# IO_Shield.net
KiCad netlist of a schematic drawn in EAGLE
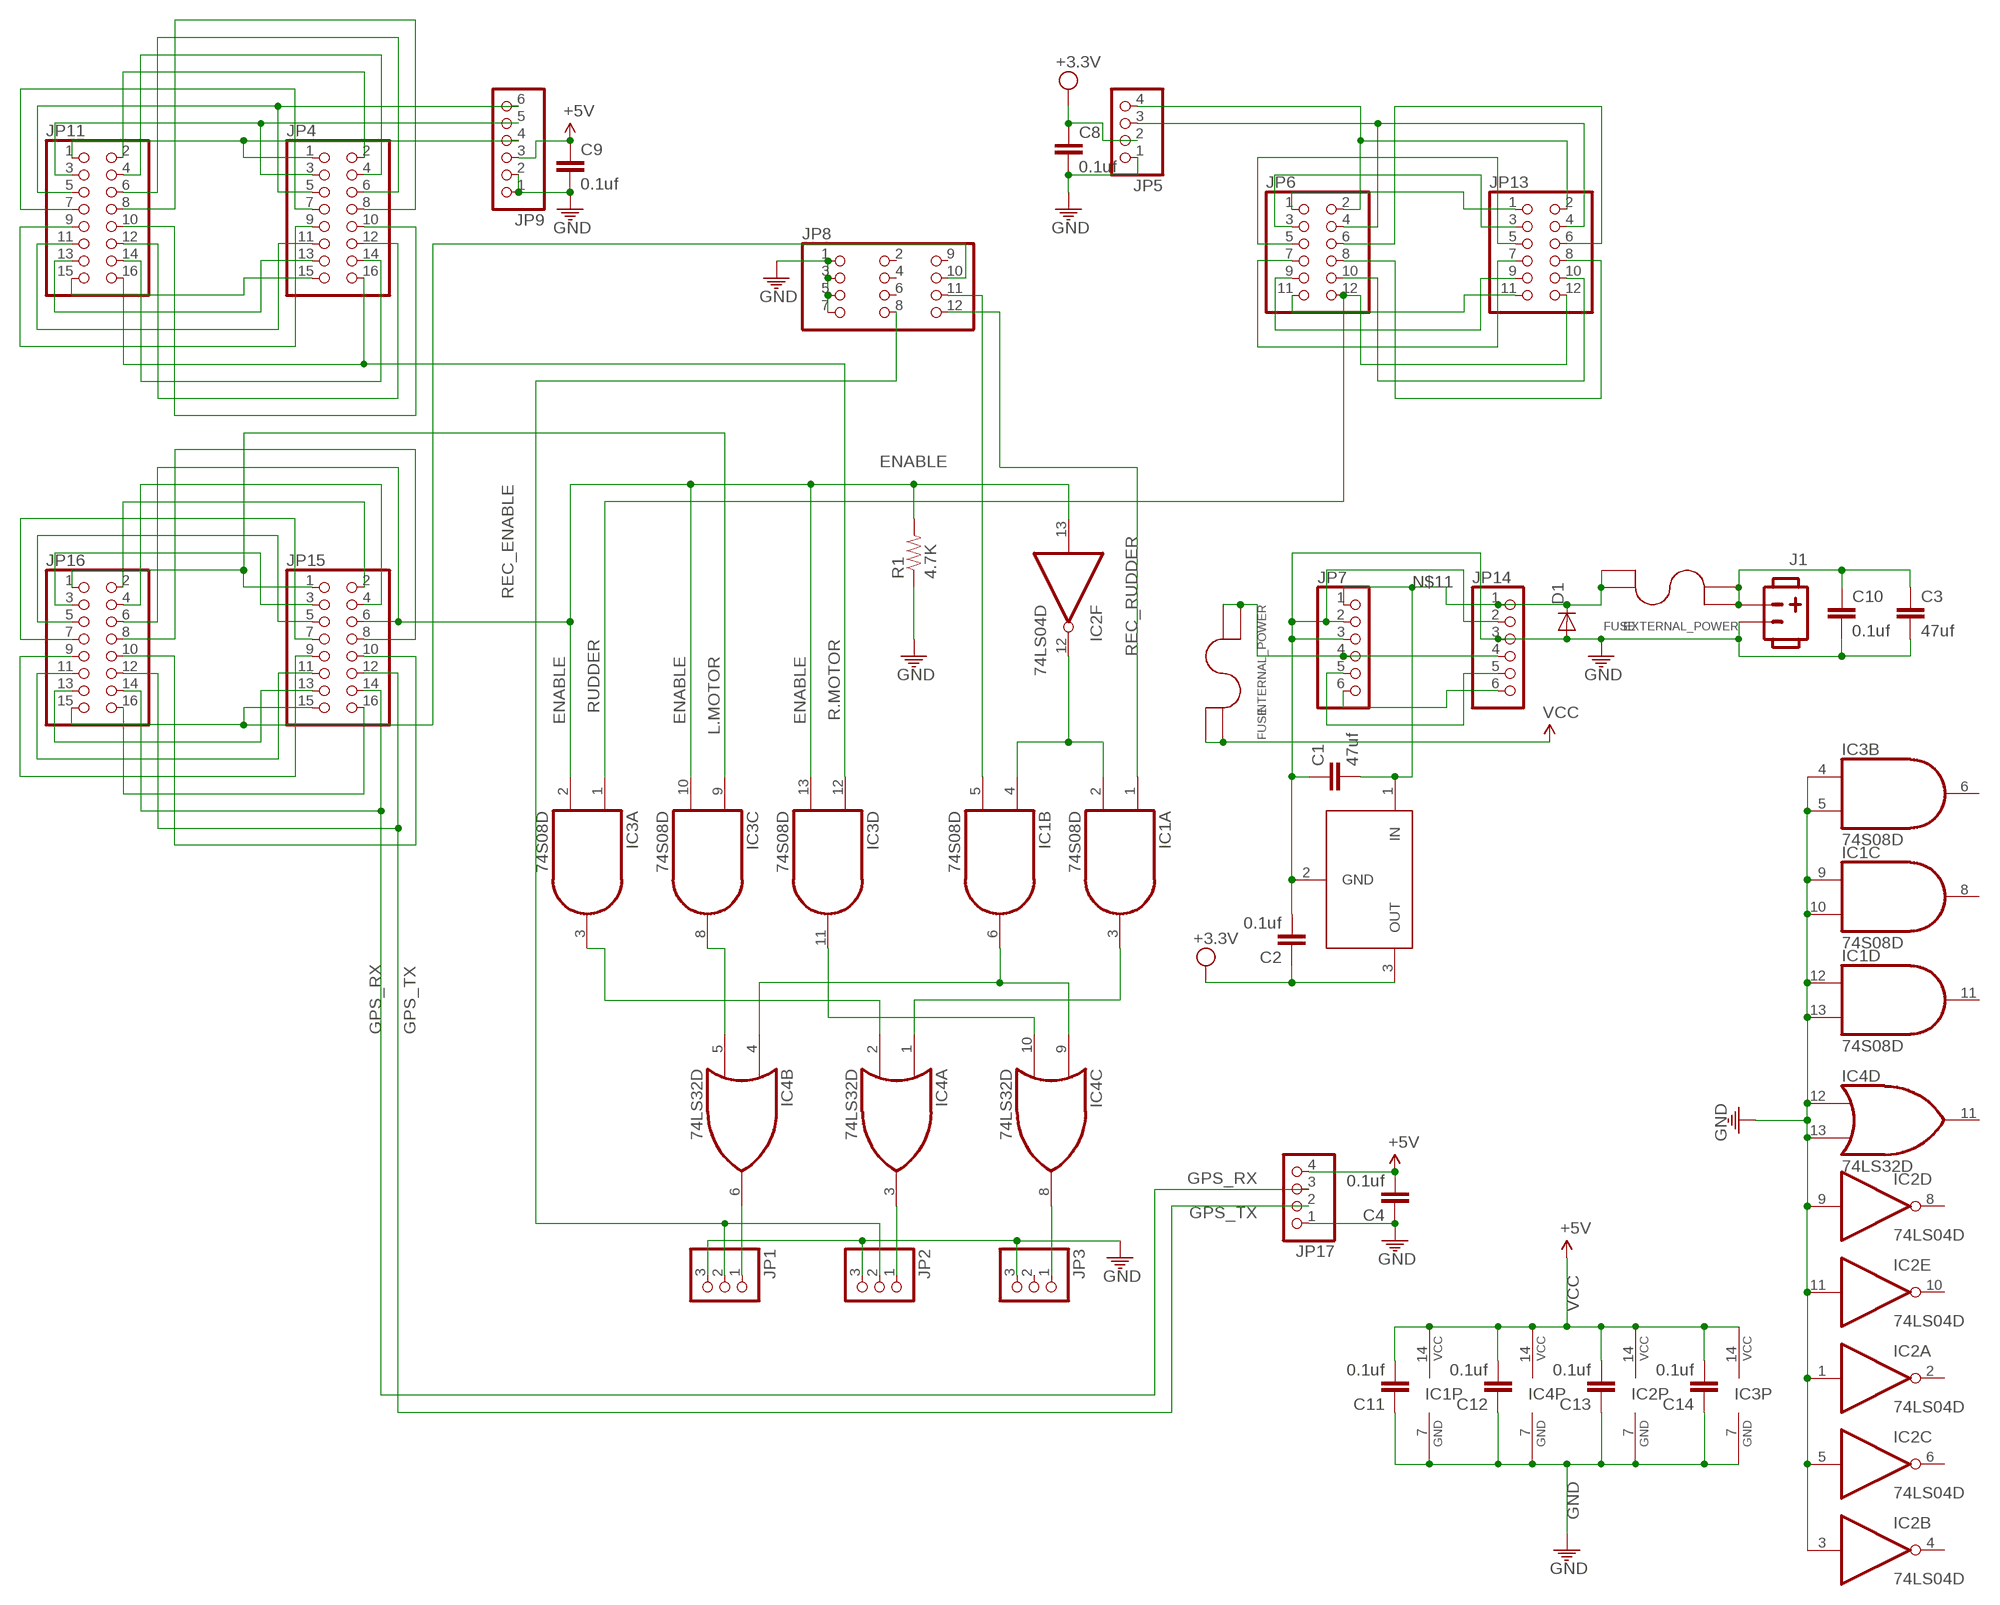
[diagram p0: schematic, sheet 1]

(export (version "E")
  (design (tool "Eeschema 10.0.6"))
  (components
    (comp (ref "C1")
      (value "47uf")
      (footprint "eagle-import:C0805")
      (libsource (lib "eagle-import") (part "C-EUC0805"))
    )
    (comp (ref "C2")
      (value "0.1uf")
      (footprint "eagle-import:C0805")
      (libsource (lib "eagle-import") (part "C-EUC0805"))
    )
    (comp (ref "C3")
      (value "47uf")
      (footprint "eagle-import:C0805")
      (libsource (lib "eagle-import") (part "C-EUC0805"))
    )
    (comp (ref "C4")
      (value "0.1uf")
      (footprint "eagle-import:C0805")
      (libsource (lib "eagle-import") (part "C-EUC0805"))
    )
    (comp (ref "C8")
      (value "0.1uf")
      (footprint "eagle-import:C0805")
      (libsource (lib "eagle-import") (part "C-EUC0805"))
    )
    (comp (ref "C9")
      (value "0.1uf")
      (footprint "eagle-import:C0805")
      (libsource (lib "eagle-import") (part "C-EUC0805"))
    )
    (comp (ref "C10")
      (value "0.1uf")
      (footprint "eagle-import:C0805")
      (libsource (lib "eagle-import") (part "C-EUC0805"))
    )
    (comp (ref "C11")
      (value "0.1uf")
      (footprint "eagle-import:C0805")
      (libsource (lib "eagle-import") (part "C-EUC0805"))
    )
    (comp (ref "C12")
      (value "0.1uf")
      (footprint "eagle-import:C0805")
      (libsource (lib "eagle-import") (part "C-EUC0805"))
    )
    (comp (ref "C13")
      (value "0.1uf")
      (footprint "eagle-import:C0805")
      (libsource (lib "eagle-import") (part "C-EUC0805"))
    )
    (comp (ref "C14")
      (value "0.1uf")
      (footprint "eagle-import:C0805")
      (libsource (lib "eagle-import") (part "C-EUC0805"))
    )
    (comp (ref "D1")
      (value "DIODEPTH")
      (footprint "eagle-import:DIODE-1N4001")
      (libsource (lib "eagle-import") (part "DIODEPTH"))
    )
    (comp (ref "EXTERNAL_POWER")
      (value "FUSE")
      (footprint "eagle-import:FUSE_2AG")
      (libsource (lib "eagle-import") (part "FUSE"))
    )
    (comp (ref "IC1")
      (value "74S08D")
      (footprint "eagle-import:SO14")
      (libsource (lib "eagle-import") (part "7408DS"))
    )
    (comp (ref "IC2")
      (value "74LS04D")
      (footprint "eagle-import:SO14")
      (libsource (lib "eagle-import") (part "7404DLS"))
    )
    (comp (ref "IC3")
      (value "74S08D")
      (footprint "eagle-import:SO14")
      (libsource (lib "eagle-import") (part "7408DS"))
    )
    (comp (ref "IC4")
      (value "74LS32D")
      (footprint "eagle-import:SO14")
      (libsource (lib "eagle-import") (part "7432DLS"))
    )
    (comp (ref "INTERNAL_POWER")
      (value "FUSE")
      (footprint "eagle-import:FUSE_2AG")
      (libsource (lib "eagle-import") (part "FUSE"))
    )
    (comp (ref "J1")
      (value "POW_CONNECTFEMALE-RA")
      (footprint "eagle-import:SOCKET-FEMALE_RA-3.96MM-2")
      (libsource (lib "eagle-import") (part "POW_CONNECTFEMALE-RA"))
    )
    (comp (ref "JP1")
      (value "PINHD-1X3/90")
      (footprint "eagle-import:1X03_90")
      (libsource (lib "eagle-import") (part "PINHD-1X3/90"))
    )
    (comp (ref "JP2")
      (value "PINHD-1X3/90")
      (footprint "eagle-import:1X03_90")
      (libsource (lib "eagle-import") (part "PINHD-1X3/90"))
    )
    (comp (ref "JP3")
      (value "PINHD-1X3/90")
      (footprint "eagle-import:1X03_90")
      (libsource (lib "eagle-import") (part "PINHD-1X3/90"))
    )
    (comp (ref "JP4")
      (value "PINHD-2X8")
      (footprint "eagle-import:2X08")
      (libsource (lib "eagle-import") (part "PINHD-2X8"))
    )
    (comp (ref "JP5")
      (value "PINHD-1X4")
      (footprint "eagle-import:1X04")
      (libsource (lib "eagle-import") (part "PINHD-1X4"))
    )
    (comp (ref "JP6")
      (value "PINHD-2X6")
      (footprint "eagle-import:2X06")
      (libsource (lib "eagle-import") (part "PINHD-2X6"))
    )
    (comp (ref "JP7")
      (value "PINHD-1X6")
      (footprint "eagle-import:1X06")
      (libsource (lib "eagle-import") (part "pinhead_PINHD-1X6"))
    )
    (comp (ref "JP8")
      (value "PINHD-2X4")
      (footprint "eagle-import:2X04")
      (libsource (lib "eagle-import") (part "PINHD-2X4"))
    )
    (comp (ref "JP9")
      (value "PINHD-1X6")
      (footprint "eagle-import:1X06")
      (libsource (lib "eagle-import") (part "PINHD-1X6"))
    )
    (comp (ref "JP11")
      (value "PINHD-2X8")
      (footprint "eagle-import:2X08")
      (libsource (lib "eagle-import") (part "PINHD-2X8"))
    )
    (comp (ref "JP13")
      (value "PINHD-2X6")
      (footprint "eagle-import:2X06")
      (libsource (lib "eagle-import") (part "PINHD-2X6"))
    )
    (comp (ref "JP14")
      (value "PINHD-1X6")
      (footprint "eagle-import:1X06")
      (libsource (lib "eagle-import") (part "pinhead_PINHD-1X6"))
    )
    (comp (ref "JP15")
      (value "PINHD-2X8")
      (footprint "eagle-import:2X08")
      (libsource (lib "eagle-import") (part "PINHD-2X8"))
    )
    (comp (ref "JP16")
      (value "PINHD-2X8")
      (footprint "eagle-import:2X08")
      (libsource (lib "eagle-import") (part "PINHD-2X8"))
    )
    (comp (ref "JP17")
      (value "PINHD-1X4")
      (footprint "eagle-import:1X04")
      (libsource (lib "eagle-import") (part "pinhead_PINHD-1X4"))
    )
    (comp (ref "R1")
      (value "4.7K")
      (footprint "eagle-import:0805")
      (libsource (lib "eagle-import") (part "RESISTOR0805-RES"))
    )
    (comp (ref "U$1")
      (value "LM3940IMP-3.3")
      (footprint "eagle-import:SOT223")
      (libsource (lib "eagle-import") (part "LM3940IMP-3.3"))
    )
  )
  (nets
    (net (code "1") (name "+3.3V") (class "Default")
      (node (ref "C2") (pin "1") (pinfunction "1_1") (pintype "passive"))
      (node (ref "C8") (pin "1") (pinfunction "1_1") (pintype "passive"))
      (node (ref "JP5") (pin "2") (pinfunction "2_2") (pintype "passive"))
      (node (ref "U$1") (pin "3") (pinfunction "OUT_3") (pintype "power_in"))
    )
    (net (code "2") (name "+5V") (class "Default")
      (node (ref "C11") (pin "2") (pinfunction "2_2") (pintype "passive"))
      (node (ref "C12") (pin "2") (pinfunction "2_2") (pintype "passive"))
      (node (ref "C13") (pin "2") (pinfunction "2_2") (pintype "passive"))
      (node (ref "C14") (pin "2") (pinfunction "2_2") (pintype "passive"))
      (node (ref "C4") (pin "2") (pinfunction "2_2") (pintype "passive"))
      (node (ref "C9") (pin "1") (pinfunction "1_1") (pintype "passive"))
      (node (ref "IC1") (pin "14") (pinfunction "VCC_14") (pintype "power_in"))
      (node (ref "IC2") (pin "14") (pinfunction "VCC_14") (pintype "power_in"))
      (node (ref "IC3") (pin "14") (pinfunction "VCC_14") (pintype "power_in"))
      (node (ref "IC4") (pin "14") (pinfunction "VCC_14") (pintype "power_in"))
      (node (ref "INTERNAL_POWER") (pin "P$3") (pinfunction "3_P$3") (pintype "bidirectional"))
      (node (ref "INTERNAL_POWER") (pin "P$4") (pinfunction "4_P$4") (pintype "bidirectional"))
      (node (ref "JP17") (pin "4") (pinfunction "4_4") (pintype "passive"))
      (node (ref "JP9") (pin "3") (pinfunction "3_3") (pintype "passive"))
    )
    (net (code "3") (name "/ENABLE") (class "Default")
      (node (ref "IC2") (pin "13") (pinfunction "I_13") (pintype "input"))
      (node (ref "IC3") (pin "10") (pinfunction "I1_10") (pintype "input"))
      (node (ref "IC3") (pin "13") (pinfunction "I1_13") (pintype "input"))
      (node (ref "IC3") (pin "2") (pinfunction "I1_2") (pintype "input"))
      (node (ref "JP15") (pin "6") (pinfunction "6_6") (pintype "passive"))
      (node (ref "JP16") (pin "6") (pinfunction "6_6") (pintype "passive"))
      (node (ref "R1") (pin "2") (pinfunction "2_2") (pintype "passive"))
    )
    (net (code "4") (name "/GPS_RX") (class "Default")
      (node (ref "JP15") (pin "14") (pinfunction "14_14") (pintype "passive"))
      (node (ref "JP16") (pin "14") (pinfunction "14_14") (pintype "passive"))
      (node (ref "JP17") (pin "3") (pinfunction "3_3") (pintype "passive"))
    )
    (net (code "5") (name "/GPS_TX") (class "Default")
      (node (ref "JP15") (pin "12") (pinfunction "12_12") (pintype "passive"))
      (node (ref "JP16") (pin "12") (pinfunction "12_12") (pintype "passive"))
      (node (ref "JP17") (pin "2") (pinfunction "2_2") (pintype "passive"))
    )
    (net (code "6") (name "/L.MOTOR") (class "Default")
      (node (ref "IC3") (pin "9") (pinfunction "I0_9") (pintype "input"))
      (node (ref "JP15") (pin "1") (pinfunction "1_1") (pintype "passive"))
      (node (ref "JP16") (pin "1") (pinfunction "1_1") (pintype "passive"))
    )
    (net (code "7") (name "/N$11") (class "Default")
      (node (ref "C1") (pin "2") (pinfunction "2_2") (pintype "passive"))
      (node (ref "D1") (pin "C") (pinfunction "C_C") (pintype "passive"))
      (node (ref "EXTERNAL_POWER") (pin "P$3") (pinfunction "3_P$3") (pintype "bidirectional"))
      (node (ref "EXTERNAL_POWER") (pin "P$4") (pinfunction "4_P$4") (pintype "bidirectional"))
      (node (ref "JP14") (pin "1") (pinfunction "1_1") (pintype "passive"))
      (node (ref "JP7") (pin "1") (pinfunction "1_1") (pintype "passive"))
      (node (ref "U$1") (pin "1") (pinfunction "IN_1") (pintype "power_in"))
    )
    (net (code "8") (name "/R.MOTOR") (class "Default")
      (node (ref "IC3") (pin "12") (pinfunction "I0_12") (pintype "input"))
      (node (ref "JP11") (pin "16") (pinfunction "16_16") (pintype "passive"))
      (node (ref "JP4") (pin "16") (pinfunction "16_16") (pintype "passive"))
    )
    (net (code "9") (name "/REC_ENABLE") (class "Default")
      (node (ref "JP15") (pin "16") (pinfunction "16_16") (pintype "passive"))
      (node (ref "JP16") (pin "16") (pinfunction "16_16") (pintype "passive"))
    )
    (net (code "10") (name "/REC_RUDDER") (class "Default")
      (node (ref "IC1") (pin "1") (pinfunction "I0_1") (pintype "input"))
      (node (ref "JP8") (pin "12") (pinfunction "12_12") (pintype "passive"))
    )
    (net (code "11") (name "/RUDDER") (class "Default")
      (node (ref "IC3") (pin "1") (pinfunction "I0_1") (pintype "input"))
      (node (ref "JP13") (pin "12") (pinfunction "12_12") (pintype "passive"))
      (node (ref "JP6") (pin "12") (pinfunction "12_12") (pintype "passive"))
    )
    (net (code "12") (name "GND") (class "Default")
      (node (ref "C1") (pin "1") (pinfunction "1_1") (pintype "passive"))
      (node (ref "C10") (pin "2") (pinfunction "2_2") (pintype "passive"))
      (node (ref "C11") (pin "1") (pinfunction "1_1") (pintype "passive"))
      (node (ref "C12") (pin "1") (pinfunction "1_1") (pintype "passive"))
      (node (ref "C13") (pin "1") (pinfunction "1_1") (pintype "passive"))
      (node (ref "C14") (pin "1") (pinfunction "1_1") (pintype "passive"))
      (node (ref "C2") (pin "2") (pinfunction "2_2") (pintype "passive"))
      (node (ref "C3") (pin "2") (pinfunction "2_2") (pintype "passive"))
      (node (ref "C4") (pin "1") (pinfunction "1_1") (pintype "passive"))
      (node (ref "C8") (pin "2") (pinfunction "2_2") (pintype "passive"))
      (node (ref "C9") (pin "2") (pinfunction "2_2") (pintype "passive"))
      (node (ref "D1") (pin "A") (pinfunction "A_A") (pintype "passive"))
      (node (ref "IC1") (pin "10") (pinfunction "I1_10") (pintype "input"))
      (node (ref "IC1") (pin "12") (pinfunction "I0_12") (pintype "input"))
      (node (ref "IC1") (pin "13") (pinfunction "I1_13") (pintype "input"))
      (node (ref "IC1") (pin "7") (pinfunction "GND_7") (pintype "power_in"))
      (node (ref "IC1") (pin "9") (pinfunction "I0_9") (pintype "input"))
      (node (ref "IC2") (pin "1") (pinfunction "I_1") (pintype "input"))
      (node (ref "IC2") (pin "11") (pinfunction "I_11") (pintype "input"))
      (node (ref "IC2") (pin "3") (pinfunction "I_3") (pintype "input"))
      (node (ref "IC2") (pin "5") (pinfunction "I_5") (pintype "input"))
      (node (ref "IC2") (pin "7") (pinfunction "GND_7") (pintype "power_in"))
      (node (ref "IC2") (pin "9") (pinfunction "I_9") (pintype "input"))
      (node (ref "IC3") (pin "4") (pinfunction "I0_4") (pintype "input"))
      (node (ref "IC3") (pin "5") (pinfunction "I1_5") (pintype "input"))
      (node (ref "IC3") (pin "7") (pinfunction "GND_7") (pintype "power_in"))
      (node (ref "IC4") (pin "12") (pinfunction "I0_12") (pintype "input"))
      (node (ref "IC4") (pin "13") (pinfunction "I1_13") (pintype "input"))
      (node (ref "IC4") (pin "7") (pinfunction "GND_7") (pintype "power_in"))
      (node (ref "J1") (pin "2") (pinfunction "2_2") (pintype "passive"))
      (node (ref "JP1") (pin "3") (pinfunction "3_3") (pintype "passive"))
      (node (ref "JP14") (pin "2") (pinfunction "2_2") (pintype "passive"))
      (node (ref "JP14") (pin "3") (pinfunction "3_3") (pintype "passive"))
      (node (ref "JP17") (pin "1") (pinfunction "1_1") (pintype "passive"))
      (node (ref "JP2") (pin "3") (pinfunction "3_3") (pintype "passive"))
      (node (ref "JP3") (pin "3") (pinfunction "3_3") (pintype "passive"))
      (node (ref "JP5") (pin "1") (pinfunction "1_1") (pintype "passive"))
      (node (ref "JP7") (pin "2") (pinfunction "2_2") (pintype "passive"))
      (node (ref "JP7") (pin "3") (pinfunction "3_3") (pintype "passive"))
      (node (ref "JP8") (pin "1") (pinfunction "1_1") (pintype "passive"))
      (node (ref "JP8") (pin "3") (pinfunction "3_3") (pintype "passive"))
      (node (ref "JP8") (pin "5") (pinfunction "5_5") (pintype "passive"))
      (node (ref "JP8") (pin "7") (pinfunction "7_7") (pintype "passive"))
      (node (ref "JP9") (pin "1") (pinfunction "1_1") (pintype "passive"))
      (node (ref "JP9") (pin "2") (pinfunction "2_2") (pintype "passive"))
      (node (ref "R1") (pin "1") (pinfunction "1_1") (pintype "passive"))
      (node (ref "U$1") (pin "2") (pinfunction "GND_2") (pintype "power_in"))
    )
    (net (code "13") (name "Net-(EXTERNAL_POWER-1)") (class "Default")
      (node (ref "C10") (pin "1") (pinfunction "1_1") (pintype "passive"))
      (node (ref "C3") (pin "1") (pinfunction "1_1") (pintype "passive"))
      (node (ref "EXTERNAL_POWER") (pin "P$1") (pinfunction "1_P$1") (pintype "bidirectional"))
      (node (ref "EXTERNAL_POWER") (pin "P$2") (pinfunction "2_P$2") (pintype "bidirectional"))
      (node (ref "J1") (pin "1") (pinfunction "1_1") (pintype "passive"))
    )
    (net (code "14") (name "Net-(IC1A-I1)") (class "Default")
      (node (ref "IC1") (pin "2") (pinfunction "I1_2") (pintype "input"))
      (node (ref "IC1") (pin "4") (pinfunction "I0_4") (pintype "input"))
      (node (ref "IC2") (pin "12") (pinfunction "O_12") (pintype "output"))
    )
    (net (code "15") (name "Net-(IC1A-O)") (class "Default")
      (node (ref "IC1") (pin "3") (pinfunction "O_3") (pintype "output"))
      (node (ref "IC4") (pin "1") (pinfunction "I0_1") (pintype "input"))
    )
    (net (code "16") (name "Net-(IC1B-I1)") (class "Default")
      (node (ref "IC1") (pin "5") (pinfunction "I1_5") (pintype "input"))
      (node (ref "JP8") (pin "11") (pinfunction "11_11") (pintype "passive"))
    )
    (net (code "17") (name "Net-(IC1B-O)") (class "Default")
      (node (ref "IC1") (pin "6") (pinfunction "O_6") (pintype "output"))
      (node (ref "IC4") (pin "4") (pinfunction "I0_4") (pintype "input"))
      (node (ref "IC4") (pin "9") (pinfunction "I0_9") (pintype "input"))
    )
    (net (code "18") (name "Net-(IC3A-O)") (class "Default")
      (node (ref "IC3") (pin "3") (pinfunction "O_3") (pintype "output"))
      (node (ref "IC4") (pin "2") (pinfunction "I1_2") (pintype "input"))
    )
    (net (code "19") (name "Net-(IC3C-O)") (class "Default")
      (node (ref "IC3") (pin "8") (pinfunction "O_8") (pintype "output"))
      (node (ref "IC4") (pin "5") (pinfunction "I1_5") (pintype "input"))
    )
    (net (code "20") (name "Net-(IC3D-O)") (class "Default")
      (node (ref "IC3") (pin "11") (pinfunction "O_11") (pintype "output"))
      (node (ref "IC4") (pin "10") (pinfunction "I1_10") (pintype "input"))
    )
    (net (code "21") (name "Net-(IC4A-O)") (class "Default")
      (node (ref "IC4") (pin "3") (pinfunction "O_3") (pintype "output"))
      (node (ref "JP2") (pin "1") (pinfunction "1_1") (pintype "passive"))
    )
    (net (code "22") (name "Net-(IC4B-O)") (class "Default")
      (node (ref "IC4") (pin "6") (pinfunction "O_6") (pintype "output"))
      (node (ref "JP1") (pin "1") (pinfunction "1_1") (pintype "passive"))
    )
    (net (code "23") (name "Net-(IC4C-O)") (class "Default")
      (node (ref "IC4") (pin "8") (pinfunction "O_8") (pintype "output"))
      (node (ref "JP3") (pin "1") (pinfunction "1_1") (pintype "passive"))
    )
    (net (code "24") (name "Net-(INTERNAL_POWER-1)") (class "Default")
      (node (ref "INTERNAL_POWER") (pin "P$1") (pinfunction "1_P$1") (pintype "bidirectional"))
      (node (ref "INTERNAL_POWER") (pin "P$2") (pinfunction "2_P$2") (pintype "bidirectional"))
      (node (ref "JP14") (pin "4") (pinfunction "4_4") (pintype "passive"))
      (node (ref "JP7") (pin "4") (pinfunction "4_4") (pintype "passive"))
    )
    (net (code "25") (name "Net-(JP1-Pad2)") (class "Default")
      (node (ref "JP1") (pin "2") (pinfunction "2_2") (pintype "passive"))
      (node (ref "JP2") (pin "2") (pinfunction "2_2") (pintype "passive"))
      (node (ref "JP8") (pin "8") (pinfunction "8_8") (pintype "passive"))
    )
    (net (code "26") (name "Net-(JP8-9)") (class "Default")
      (node (ref "JP15") (pin "15") (pinfunction "15_15") (pintype "passive"))
      (node (ref "JP16") (pin "15") (pinfunction "15_15") (pintype "passive"))
      (node (ref "JP8") (pin "10") (pinfunction "9_10") (pintype "passive"))
    )
    (net (code "27") (name "Net-(JP11-Pad1)") (class "Default")
      (node (ref "JP11") (pin "1") (pinfunction "1_1") (pintype "passive"))
      (node (ref "JP4") (pin "1") (pinfunction "1_1") (pintype "passive"))
      (node (ref "JP9") (pin "4") (pinfunction "4_4") (pintype "passive"))
    )
    (net (code "28") (name "Net-(JP11-Pad2)") (class "Default")
      (node (ref "JP11") (pin "2") (pinfunction "2_2") (pintype "passive"))
      (node (ref "JP4") (pin "2") (pinfunction "2_2") (pintype "passive"))
    )
    (net (code "29") (name "Net-(JP11-Pad3)") (class "Default")
      (node (ref "JP11") (pin "3") (pinfunction "3_3") (pintype "passive"))
      (node (ref "JP4") (pin "3") (pinfunction "3_3") (pintype "passive"))
      (node (ref "JP9") (pin "5") (pinfunction "5_5") (pintype "passive"))
    )
    (net (code "30") (name "Net-(JP11-Pad4)") (class "Default")
      (node (ref "JP11") (pin "4") (pinfunction "4_4") (pintype "passive"))
      (node (ref "JP4") (pin "4") (pinfunction "4_4") (pintype "passive"))
    )
    (net (code "31") (name "Net-(JP11-Pad5)") (class "Default")
      (node (ref "JP11") (pin "5") (pinfunction "5_5") (pintype "passive"))
      (node (ref "JP4") (pin "5") (pinfunction "5_5") (pintype "passive"))
      (node (ref "JP9") (pin "6") (pinfunction "6_6") (pintype "passive"))
    )
    (net (code "32") (name "Net-(JP11-Pad6)") (class "Default")
      (node (ref "JP11") (pin "6") (pinfunction "6_6") (pintype "passive"))
      (node (ref "JP4") (pin "6") (pinfunction "6_6") (pintype "passive"))
    )
    (net (code "33") (name "Net-(JP11-Pad7)") (class "Default")
      (node (ref "JP11") (pin "7") (pinfunction "7_7") (pintype "passive"))
      (node (ref "JP4") (pin "7") (pinfunction "7_7") (pintype "passive"))
    )
    (net (code "34") (name "Net-(JP11-Pad8)") (class "Default")
      (node (ref "JP11") (pin "8") (pinfunction "8_8") (pintype "passive"))
      (node (ref "JP4") (pin "8") (pinfunction "8_8") (pintype "passive"))
    )
    (net (code "35") (name "Net-(JP11-Pad9)") (class "Default")
      (node (ref "JP11") (pin "9") (pinfunction "9_9") (pintype "passive"))
      (node (ref "JP4") (pin "9") (pinfunction "9_9") (pintype "passive"))
    )
    (net (code "36") (name "Net-(JP11-Pad10)") (class "Default")
      (node (ref "JP11") (pin "10") (pinfunction "10_10") (pintype "passive"))
      (node (ref "JP4") (pin "10") (pinfunction "10_10") (pintype "passive"))
    )
    (net (code "37") (name "Net-(JP11-Pad11)") (class "Default")
      (node (ref "JP11") (pin "11") (pinfunction "11_11") (pintype "passive"))
      (node (ref "JP4") (pin "11") (pinfunction "11_11") (pintype "passive"))
    )
    (net (code "38") (name "Net-(JP11-Pad12)") (class "Default")
      (node (ref "JP11") (pin "12") (pinfunction "12_12") (pintype "passive"))
      (node (ref "JP4") (pin "12") (pinfunction "12_12") (pintype "passive"))
    )
    (net (code "39") (name "Net-(JP11-Pad13)") (class "Default")
      (node (ref "JP11") (pin "13") (pinfunction "13_13") (pintype "passive"))
      (node (ref "JP4") (pin "13") (pinfunction "13_13") (pintype "passive"))
    )
    (net (code "40") (name "Net-(JP11-Pad14)") (class "Default")
      (node (ref "JP11") (pin "14") (pinfunction "14_14") (pintype "passive"))
      (node (ref "JP4") (pin "14") (pinfunction "14_14") (pintype "passive"))
    )
    (net (code "41") (name "Net-(JP11-Pad15)") (class "Default")
      (node (ref "JP11") (pin "15") (pinfunction "15_15") (pintype "passive"))
      (node (ref "JP4") (pin "15") (pinfunction "15_15") (pintype "passive"))
    )
    (net (code "42") (name "Net-(JP13-Pad1)") (class "Default")
      (node (ref "JP13") (pin "1") (pinfunction "1_1") (pintype "passive"))
      (node (ref "JP6") (pin "1") (pinfunction "1_1") (pintype "passive"))
    )
    (net (code "43") (name "Net-(JP13-Pad2)") (class "Default")
      (node (ref "JP13") (pin "2") (pinfunction "2_2") (pintype "passive"))
      (node (ref "JP5") (pin "4") (pinfunction "4_4") (pintype "passive"))
      (node (ref "JP6") (pin "2") (pinfunction "2_2") (pintype "passive"))
    )
    (net (code "44") (name "Net-(JP13-Pad3)") (class "Default")
      (node (ref "JP13") (pin "3") (pinfunction "3_3") (pintype "passive"))
      (node (ref "JP6") (pin "3") (pinfunction "3_3") (pintype "passive"))
    )
    (net (code "45") (name "Net-(JP13-Pad4)") (class "Default")
      (node (ref "JP13") (pin "4") (pinfunction "4_4") (pintype "passive"))
      (node (ref "JP5") (pin "3") (pinfunction "3_3") (pintype "passive"))
      (node (ref "JP6") (pin "4") (pinfunction "4_4") (pintype "passive"))
    )
    (net (code "46") (name "Net-(JP13-Pad5)") (class "Default")
      (node (ref "JP13") (pin "5") (pinfunction "5_5") (pintype "passive"))
      (node (ref "JP6") (pin "5") (pinfunction "5_5") (pintype "passive"))
    )
    (net (code "47") (name "Net-(JP13-Pad6)") (class "Default")
      (node (ref "JP13") (pin "6") (pinfunction "6_6") (pintype "passive"))
      (node (ref "JP6") (pin "6") (pinfunction "6_6") (pintype "passive"))
    )
    (net (code "48") (name "Net-(JP13-Pad7)") (class "Default")
      (node (ref "JP13") (pin "7") (pinfunction "7_7") (pintype "passive"))
      (node (ref "JP6") (pin "7") (pinfunction "7_7") (pintype "passive"))
    )
    (net (code "49") (name "Net-(JP13-Pad8)") (class "Default")
      (node (ref "JP13") (pin "8") (pinfunction "8_8") (pintype "passive"))
      (node (ref "JP6") (pin "8") (pinfunction "8_8") (pintype "passive"))
    )
    (net (code "50") (name "Net-(JP13-Pad9)") (class "Default")
      (node (ref "JP13") (pin "9") (pinfunction "9_9") (pintype "passive"))
      (node (ref "JP6") (pin "9") (pinfunction "9_9") (pintype "passive"))
    )
    (net (code "51") (name "Net-(JP13-Pad10)") (class "Default")
      (node (ref "JP13") (pin "10") (pinfunction "10_10") (pintype "passive"))
      (node (ref "JP6") (pin "10") (pinfunction "10_10") (pintype "passive"))
    )
    (net (code "52") (name "Net-(JP13-Pad11)") (class "Default")
      (node (ref "JP13") (pin "11") (pinfunction "11_11") (pintype "passive"))
      (node (ref "JP6") (pin "11") (pinfunction "11_11") (pintype "passive"))
    )
    (net (code "53") (name "Net-(JP14-Pad5)") (class "Default")
      (node (ref "JP14") (pin "5") (pinfunction "5_5") (pintype "passive"))
      (node (ref "JP7") (pin "5") (pinfunction "5_5") (pintype "passive"))
    )
    (net (code "54") (name "Net-(JP14-Pad6)") (class "Default")
      (node (ref "JP14") (pin "6") (pinfunction "6_6") (pintype "passive"))
      (node (ref "JP7") (pin "6") (pinfunction "6_6") (pintype "passive"))
    )
    (net (code "55") (name "Net-(JP15-Pad2)") (class "Default")
      (node (ref "JP15") (pin "2") (pinfunction "2_2") (pintype "passive"))
      (node (ref "JP16") (pin "2") (pinfunction "2_2") (pintype "passive"))
    )
    (net (code "56") (name "Net-(JP15-Pad3)") (class "Default")
      (node (ref "JP15") (pin "3") (pinfunction "3_3") (pintype "passive"))
      (node (ref "JP16") (pin "3") (pinfunction "3_3") (pintype "passive"))
    )
    (net (code "57") (name "Net-(JP15-Pad4)") (class "Default")
      (node (ref "JP15") (pin "4") (pinfunction "4_4") (pintype "passive"))
      (node (ref "JP16") (pin "4") (pinfunction "4_4") (pintype "passive"))
    )
    (net (code "58") (name "Net-(JP15-Pad5)") (class "Default")
      (node (ref "JP15") (pin "5") (pinfunction "5_5") (pintype "passive"))
      (node (ref "JP16") (pin "5") (pinfunction "5_5") (pintype "passive"))
    )
    (net (code "59") (name "Net-(JP15-Pad7)") (class "Default")
      (node (ref "JP15") (pin "7") (pinfunction "7_7") (pintype "passive"))
      (node (ref "JP16") (pin "7") (pinfunction "7_7") (pintype "passive"))
    )
    (net (code "60") (name "Net-(JP15-Pad8)") (class "Default")
      (node (ref "JP15") (pin "8") (pinfunction "8_8") (pintype "passive"))
      (node (ref "JP16") (pin "8") (pinfunction "8_8") (pintype "passive"))
    )
    (net (code "61") (name "Net-(JP15-Pad9)") (class "Default")
      (node (ref "JP15") (pin "9") (pinfunction "9_9") (pintype "passive"))
      (node (ref "JP16") (pin "9") (pinfunction "9_9") (pintype "passive"))
    )
    (net (code "62") (name "Net-(JP15-Pad10)") (class "Default")
      (node (ref "JP15") (pin "10") (pinfunction "10_10") (pintype "passive"))
      (node (ref "JP16") (pin "10") (pinfunction "10_10") (pintype "passive"))
    )
    (net (code "63") (name "Net-(JP15-Pad11)") (class "Default")
      (node (ref "JP15") (pin "11") (pinfunction "11_11") (pintype "passive"))
      (node (ref "JP16") (pin "11") (pinfunction "11_11") (pintype "passive"))
    )
    (net (code "64") (name "Net-(JP15-Pad13)") (class "Default")
      (node (ref "JP15") (pin "13") (pinfunction "13_13") (pintype "passive"))
      (node (ref "JP16") (pin "13") (pinfunction "13_13") (pintype "passive"))
    )
    (net (code "65") (name "unconnected-(IC1C-O-Pad8)") (class "Default")
      (node (ref "IC1") (pin "8") (pinfunction "O_8") (pintype "output"))
    )
    (net (code "66") (name "unconnected-(IC1D-O-Pad11)") (class "Default")
      (node (ref "IC1") (pin "11") (pinfunction "O_11") (pintype "output"))
    )
    (net (code "67") (name "unconnected-(IC2A-O-Pad2)") (class "Default")
      (node (ref "IC2") (pin "2") (pinfunction "O_2") (pintype "output"))
    )
    (net (code "68") (name "unconnected-(IC2B-O-Pad4)") (class "Default")
      (node (ref "IC2") (pin "4") (pinfunction "O_4") (pintype "output"))
    )
    (net (code "69") (name "unconnected-(IC2C-O-Pad6)") (class "Default")
      (node (ref "IC2") (pin "6") (pinfunction "O_6") (pintype "output"))
    )
    (net (code "70") (name "unconnected-(IC2D-O-Pad8)") (class "Default")
      (node (ref "IC2") (pin "8") (pinfunction "O_8") (pintype "output"))
    )
    (net (code "71") (name "unconnected-(IC2E-O-Pad10)") (class "Default")
      (node (ref "IC2") (pin "10") (pinfunction "O_10") (pintype "output"))
    )
    (net (code "72") (name "unconnected-(IC3B-O-Pad6)") (class "Default")
      (node (ref "IC3") (pin "6") (pinfunction "O_6") (pintype "output"))
    )
    (net (code "73") (name "unconnected-(IC4D-O-Pad11)") (class "Default")
      (node (ref "IC4") (pin "11") (pinfunction "O_11") (pintype "output"))
    )
    (net (code "74") (name "unconnected-(JP3-Pad2)") (class "Default")
      (node (ref "JP3") (pin "2") (pinfunction "2_2") (pintype "passive"))
    )
    (net (code "75") (name "unconnected-(JP8-10-Pad9)") (class "Default")
      (node (ref "JP8") (pin "9") (pinfunction "10_9") (pintype "passive"))
    )
    (net (code "76") (name "unconnected-(JP8-Pad2)") (class "Default")
      (node (ref "JP8") (pin "2") (pinfunction "2_2") (pintype "passive"))
    )
    (net (code "77") (name "unconnected-(JP8-Pad4)") (class "Default")
      (node (ref "JP8") (pin "4") (pinfunction "4_4") (pintype "passive"))
    )
    (net (code "78") (name "unconnected-(JP8-Pad6)") (class "Default")
      (node (ref "JP8") (pin "6") (pinfunction "6_6") (pintype "passive"))
    )
  )
)
